# OpenProg-18F2550-etch-it.net
KiCad netlist of a schematic drawn in EAGLE
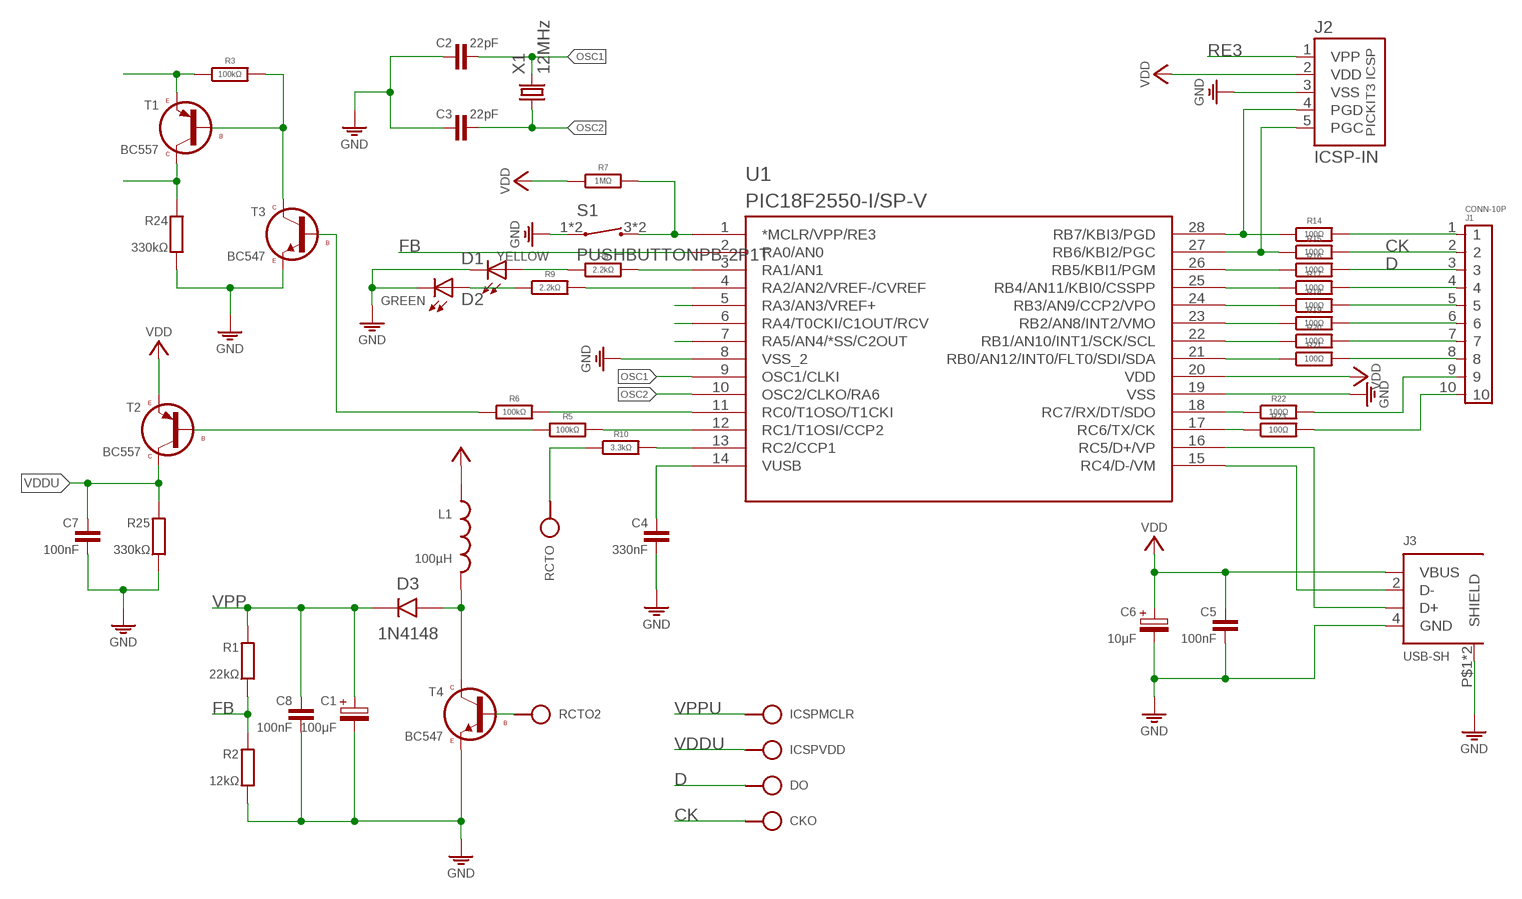
[diagram p0: schematic, sheet 1]

(export (version "E")
  (design (tool "Eeschema 10.0.6"))
  (components
    (comp (ref "C1")
      (value "100μF")
      (footprint "eagle-import:E2,5-5_V")
      (libsource (lib "eagle-import") (part "CPOLE2,5-5/V"))
    )
    (comp (ref "C2")
      (value "22pF")
      (footprint "eagle-import:C025-015X024")
      (libsource (lib "eagle-import") (part "C-H025-015X024"))
    )
    (comp (ref "C3")
      (value "22pF")
      (footprint "eagle-import:C025-015X024")
      (libsource (lib "eagle-import") (part "C-H025-015X024"))
    )
    (comp (ref "C4")
      (value "330nF")
      (footprint "eagle-import:C050-030X075")
      (libsource (lib "eagle-import") (part "C050-030X075"))
    )
    (comp (ref "C5")
      (value "100nF")
      (footprint "eagle-import:C025-015X024")
      (libsource (lib "eagle-import") (part "C025-015X024"))
    )
    (comp (ref "C6")
      (value "10μF")
      (footprint "eagle-import:E2,5-5")
      (libsource (lib "eagle-import") (part "CPOLE2.5-5"))
    )
    (comp (ref "C7")
      (value "100nF")
      (footprint "eagle-import:C050-020X036")
      (libsource (lib "eagle-import") (part "C050-020X036"))
    )
    (comp (ref "C8")
      (value "100nF")
      (footprint "eagle-import:C025-015X024")
      (libsource (lib "eagle-import") (part "C025-015X024"))
    )
    (comp (ref "CKO")
      (value "HPORT")
      (footprint "eagle-import:SPAD")
      (libsource (lib "eagle-import") (part "HPORT"))
    )
    (comp (ref "D1")
      (value "YELLOW")
      (footprint "eagle-import:LED_3MM")
      (libsource (lib "eagle-import") (part "LED-3MM"))
    )
    (comp (ref "D2")
      (value "GREEN")
      (footprint "eagle-import:LED_3MM")
      (libsource (lib "eagle-import") (part "LED-3MM"))
    )
    (comp (ref "D3")
      (value "1N4148")
      (footprint "eagle-import:DO34-7")
      (libsource (lib "eagle-import") (part "1N4148-HDO34-7"))
    )
    (comp (ref "DO")
      (value "HPORT")
      (footprint "eagle-import:SPAD")
      (libsource (lib "eagle-import") (part "HPORT"))
    )
    (comp (ref "ICSPMCLR")
      (value "HPORT")
      (footprint "eagle-import:SPAD")
      (libsource (lib "eagle-import") (part "HPORT"))
    )
    (comp (ref "ICSPVDD")
      (value "HPORT")
      (footprint "eagle-import:SPAD")
      (libsource (lib "eagle-import") (part "HPORT"))
    )
    (comp (ref "J1")
      (value "CONN-10P")
      (footprint "eagle-import:CONN-10P")
      (libsource (lib "eagle-import") (part "CONN-10P"))
    )
    (comp (ref "J2")
      (value "ICSP-IN")
      (footprint "eagle-import:PIC-PK3")
      (libsource (lib "eagle-import") (part "PICKIT3-ICSP-PK3"))
    )
    (comp (ref "J3")
      (value "USB-SH")
      (footprint "eagle-import:USB-B-PRINT")
      (libsource (lib "eagle-import") (part "USB-SH"))
    )
    (comp (ref "L1")
      (value "100µH")
      (footprint "eagle-import:L-03_10V")
      (libsource (lib "eagle-import") (part "L02/10"))
    )
    (comp (ref "R1")
      (value "22kΩ")
      (footprint "eagle-import:0204_10-V")
      (libsource (lib "eagle-import") (part "R0204/10-V"))
    )
    (comp (ref "R2")
      (value "12kΩ")
      (footprint "eagle-import:0204_10-V")
      (libsource (lib "eagle-import") (part "R0204/10-V"))
    )
    (comp (ref "R3")
      (value "100kΩ")
      (footprint "eagle-import:0204_2")
      (libsource (lib "eagle-import") (part "R-H0204/2"))
    )
    (comp (ref "R5")
      (value "100kΩ")
      (footprint "eagle-import:0204_10")
      (libsource (lib "eagle-import") (part "R-H0204/10"))
    )
    (comp (ref "R6")
      (value "100kΩ")
      (footprint "eagle-import:0204_10")
      (libsource (lib "eagle-import") (part "R-H0204/10"))
    )
    (comp (ref "R7")
      (value "1MΩ")
      (footprint "eagle-import:0204_10-V")
      (libsource (lib "eagle-import") (part "R-H0204/10-V"))
    )
    (comp (ref "R8")
      (value "2.2kΩ")
      (footprint "eagle-import:0204_10")
      (libsource (lib "eagle-import") (part "R-H0204/10"))
    )
    (comp (ref "R9")
      (value "2.2kΩ")
      (footprint "eagle-import:0204_10")
      (libsource (lib "eagle-import") (part "R-H0204/10"))
    )
    (comp (ref "R10")
      (value "3.3kΩ")
      (footprint "eagle-import:0204_10")
      (libsource (lib "eagle-import") (part "R-H0204/10"))
    )
    (comp (ref "R14")
      (value "100Ω")
      (footprint "eagle-import:0204_10")
      (libsource (lib "eagle-import") (part "R-H0204/10"))
    )
    (comp (ref "R15")
      (value "100Ω")
      (footprint "eagle-import:0204_10")
      (libsource (lib "eagle-import") (part "R-H0204/10"))
    )
    (comp (ref "R16")
      (value "100Ω")
      (footprint "eagle-import:0204_10")
      (libsource (lib "eagle-import") (part "R-H0204/10"))
    )
    (comp (ref "R17")
      (value "100Ω")
      (footprint "eagle-import:0204_10")
      (libsource (lib "eagle-import") (part "R-H0204/10"))
    )
    (comp (ref "R18")
      (value "100Ω")
      (footprint "eagle-import:0204_10")
      (libsource (lib "eagle-import") (part "R-H0204/10"))
    )
    (comp (ref "R19")
      (value "100Ω")
      (footprint "eagle-import:0204_10")
      (libsource (lib "eagle-import") (part "R-H0204/10"))
    )
    (comp (ref "R20")
      (value "100Ω")
      (footprint "eagle-import:0204_10")
      (libsource (lib "eagle-import") (part "R-H0204/10"))
    )
    (comp (ref "R21")
      (value "100Ω")
      (footprint "eagle-import:0204_10")
      (libsource (lib "eagle-import") (part "R-H0204/10"))
    )
    (comp (ref "R22")
      (value "100Ω")
      (footprint "eagle-import:0204_10")
      (libsource (lib "eagle-import") (part "R-H0204/10"))
    )
    (comp (ref "R23")
      (value "100Ω")
      (footprint "eagle-import:0204_10")
      (libsource (lib "eagle-import") (part "R-H0204/10"))
    )
    (comp (ref "R24")
      (value "330kΩ")
      (footprint "eagle-import:0204_10-V")
      (libsource (lib "eagle-import") (part "R0204/10-V"))
    )
    (comp (ref "R25")
      (value "330kΩ")
      (footprint "eagle-import:0204_10-V")
      (libsource (lib "eagle-import") (part "R0204/10-V"))
    )
    (comp (ref "RCTO")
      (value "HPORT")
      (footprint "eagle-import:SPAD")
      (libsource (lib "eagle-import") (part "HPORT"))
    )
    (comp (ref "RCTO2")
      (value "HPORT")
      (footprint "eagle-import:SPAD")
      (libsource (lib "eagle-import") (part "HPORT"))
    )
    (comp (ref "S1")
      (value "PUSHBUTTONPB-2P1T")
      (footprint "eagle-import:PB-2P1T")
      (libsource (lib "eagle-import") (part "PUSHBUTTONPB-2P1T"))
    )
    (comp (ref "T1")
      (value "BC557")
      (footprint "eagle-import:TO92-CBE")
      (libsource (lib "eagle-import") (part "BC557CBE"))
    )
    (comp (ref "T2")
      (value "BC557")
      (footprint "eagle-import:TO92-CBE")
      (libsource (lib "eagle-import") (part "BC557CBE"))
    )
    (comp (ref "T3")
      (value "BC547")
      (footprint "eagle-import:TO92")
      (libsource (lib "eagle-import") (part "BC547"))
    )
    (comp (ref "T4")
      (value "BC547")
      (footprint "eagle-import:TO92")
      (libsource (lib "eagle-import") (part "BC547"))
    )
    (comp (ref "U1")
      (value "PIC18F2550-I/SP-V")
      (footprint "eagle-import:DIL28-3_V")
      (libsource (lib "eagle-import") (part "PIC18F2550-I/SP-V"))
    )
    (comp (ref "X1")
      (value "12MHz")
      (footprint "eagle-import:HC49")
      (libsource (lib "eagle-import") (part "CRYSTALHC49"))
    )
  )
  (nets
    (net (code "1") (name "/CK") (class "Default")
      (node (ref "CKO") (pin "1") (pinfunction "P$1_1") (pintype "passive"))
      (node (ref "J1") (pin "2") (pinfunction "2_2") (pintype "passive"))
      (node (ref "R15") (pin "2") (pinfunction "2_2") (pintype "passive"))
    )
    (net (code "2") (name "/D") (class "Default")
      (node (ref "DO") (pin "1") (pinfunction "P$1_1") (pintype "passive"))
      (node (ref "J1") (pin "3") (pinfunction "3_3") (pintype "passive"))
      (node (ref "R16") (pin "2") (pinfunction "2_2") (pintype "passive"))
    )
    (net (code "3") (name "/FB") (class "Default")
      (node (ref "R1") (pin "2") (pinfunction "1_2") (pintype "passive"))
      (node (ref "R2") (pin "1") (pinfunction "2_1") (pintype "passive"))
      (node (ref "U1") (pin "2") (pinfunction "RA0/AN0_2") (pintype "passive"))
    )
    (net (code "4") (name "/RE3") (class "Default")
      (node (ref "J2") (pin "1") (pinfunction "VPP_1") (pintype "passive"))
      (node (ref "R7") (pin "2") (pinfunction "2_2") (pintype "passive"))
      (node (ref "S1") (pin "3") (pinfunction "2_3") (pintype "passive"))
      (node (ref "S1") (pin "4") (pinfunction "2_4") (pintype "passive"))
      (node (ref "U1") (pin "1") (pinfunction "*MCLR/VPP/RE3_1") (pintype "passive"))
    )
    (net (code "5") (name "/VPP") (class "Default")
      (node (ref "C1") (pin "+") (pinfunction "+_+") (pintype "passive"))
      (node (ref "C8") (pin "1") (pinfunction "1_1") (pintype "passive"))
      (node (ref "D3") (pin "C") (pinfunction "C_C") (pintype "passive"))
      (node (ref "R1") (pin "1") (pinfunction "2_1") (pintype "passive"))
      (node (ref "R3") (pin "1") (pinfunction "1_1") (pintype "passive"))
      (node (ref "T1") (pin "3") (pinfunction "E_3") (pintype "passive"))
    )
    (net (code "6") (name "/VPPU") (class "Default")
      (node (ref "ICSPMCLR") (pin "1") (pinfunction "P$1_1") (pintype "passive"))
      (node (ref "R24") (pin "1") (pinfunction "2_1") (pintype "passive"))
      (node (ref "T1") (pin "1") (pinfunction "C_1") (pintype "passive"))
    )
    (net (code "7") (name "GND") (class "Default")
      (node (ref "C1") (pin "-") (pinfunction "-_-") (pintype "passive"))
      (node (ref "C2") (pin "1") (pinfunction "1_1") (pintype "passive"))
      (node (ref "C3") (pin "1") (pinfunction "1_1") (pintype "passive"))
      (node (ref "C4") (pin "2") (pinfunction "2_2") (pintype "passive"))
      (node (ref "C5") (pin "2") (pinfunction "2_2") (pintype "passive"))
      (node (ref "C6") (pin "-") (pinfunction "-_-") (pintype "passive"))
      (node (ref "C7") (pin "2") (pinfunction "2_2") (pintype "passive"))
      (node (ref "C8") (pin "2") (pinfunction "2_2") (pintype "passive"))
      (node (ref "D1") (pin "K") (pinfunction "C_K") (pintype "passive"))
      (node (ref "D2") (pin "K") (pinfunction "C_K") (pintype "passive"))
      (node (ref "J2") (pin "3") (pinfunction "VSS_3") (pintype "passive"))
      (node (ref "J3") (pin "4") (pinfunction "GND_4") (pintype "bidirectional"))
      (node (ref "J3") (pin "P$1") (pinfunction "SHIELD_P$1") (pintype "bidirectional"))
      (node (ref "J3") (pin "P$2") (pinfunction "SHIELD_P$2") (pintype "bidirectional"))
      (node (ref "R2") (pin "2") (pinfunction "1_2") (pintype "passive"))
      (node (ref "R24") (pin "2") (pinfunction "1_2") (pintype "passive"))
      (node (ref "R25") (pin "2") (pinfunction "1_2") (pintype "passive"))
      (node (ref "S1") (pin "1") (pinfunction "1_1") (pintype "passive"))
      (node (ref "S1") (pin "2") (pinfunction "1_2") (pintype "passive"))
      (node (ref "T3") (pin "3") (pinfunction "E_3") (pintype "passive"))
      (node (ref "T4") (pin "3") (pinfunction "E_3") (pintype "passive"))
      (node (ref "U1") (pin "19") (pinfunction "VSS_19") (pintype "passive"))
      (node (ref "U1") (pin "8") (pinfunction "VSS_2_8") (pintype "passive"))
    )
    (net (code "8") (name "Net-(D1-PadA)") (class "Default")
      (node (ref "D1") (pin "A") (pinfunction "A_A") (pintype "passive"))
      (node (ref "R8") (pin "1") (pinfunction "1_1") (pintype "passive"))
    )
    (net (code "9") (name "Net-(D2-PadA)") (class "Default")
      (node (ref "D2") (pin "A") (pinfunction "A_A") (pintype "passive"))
      (node (ref "R9") (pin "1") (pinfunction "1_1") (pintype "passive"))
    )
    (net (code "10") (name "Net-(J1-Pad1)") (class "Default")
      (node (ref "J1") (pin "1") (pinfunction "1_1") (pintype "passive"))
      (node (ref "R14") (pin "2") (pinfunction "2_2") (pintype "passive"))
    )
    (net (code "11") (name "Net-(J1-Pad4)") (class "Default")
      (node (ref "J1") (pin "4") (pinfunction "4_4") (pintype "passive"))
      (node (ref "R17") (pin "2") (pinfunction "2_2") (pintype "passive"))
    )
    (net (code "12") (name "Net-(J1-Pad5)") (class "Default")
      (node (ref "J1") (pin "5") (pinfunction "5_5") (pintype "passive"))
      (node (ref "R18") (pin "2") (pinfunction "2_2") (pintype "passive"))
    )
    (net (code "13") (name "Net-(J1-Pad6)") (class "Default")
      (node (ref "J1") (pin "6") (pinfunction "6_6") (pintype "passive"))
      (node (ref "R19") (pin "2") (pinfunction "2_2") (pintype "passive"))
    )
    (net (code "14") (name "Net-(J1-Pad7)") (class "Default")
      (node (ref "J1") (pin "7") (pinfunction "7_7") (pintype "passive"))
      (node (ref "R20") (pin "2") (pinfunction "2_2") (pintype "passive"))
    )
    (net (code "15") (name "Net-(J1-Pad8)") (class "Default")
      (node (ref "J1") (pin "8") (pinfunction "8_8") (pintype "passive"))
      (node (ref "R21") (pin "2") (pinfunction "2_2") (pintype "passive"))
    )
    (net (code "16") (name "Net-(J1-Pad9)") (class "Default")
      (node (ref "J1") (pin "9") (pinfunction "9_9") (pintype "passive"))
      (node (ref "R22") (pin "2") (pinfunction "2_2") (pintype "passive"))
    )
    (net (code "17") (name "Net-(J1-Pad10)") (class "Default")
      (node (ref "J1") (pin "10") (pinfunction "10_10") (pintype "passive"))
      (node (ref "R23") (pin "2") (pinfunction "2_2") (pintype "passive"))
    )
    (net (code "18") (name "Net-(J2-PGC)") (class "Default")
      (node (ref "J2") (pin "5") (pinfunction "PGC_5") (pintype "passive"))
      (node (ref "R15") (pin "1") (pinfunction "1_1") (pintype "passive"))
      (node (ref "U1") (pin "27") (pinfunction "RB6/KBI2/PGC_27") (pintype "passive"))
    )
    (net (code "19") (name "Net-(J2-PGD)") (class "Default")
      (node (ref "J2") (pin "4") (pinfunction "PGD_4") (pintype "passive"))
      (node (ref "R14") (pin "1") (pinfunction "1_1") (pintype "passive"))
      (node (ref "U1") (pin "28") (pinfunction "RB7/KBI3/PGD_28") (pintype "passive"))
    )
    (net (code "20") (name "Net-(J3-D+)") (class "Default")
      (node (ref "J3") (pin "3") (pinfunction "D+_3") (pintype "bidirectional"))
      (node (ref "U1") (pin "16") (pinfunction "RC5/D+/VP_16") (pintype "passive"))
    )
    (net (code "21") (name "Net-(J3-D-)") (class "Default")
      (node (ref "J3") (pin "2") (pinfunction "D-_2") (pintype "bidirectional"))
      (node (ref "U1") (pin "15") (pinfunction "RC4/D-/VM_15") (pintype "passive"))
    )
    (net (code "22") (name "Net-(RCTO-P$1)") (class "Default")
      (node (ref "R10") (pin "1") (pinfunction "1_1") (pintype "passive"))
      (node (ref "RCTO") (pin "1") (pinfunction "P$1_1") (pintype "passive"))
    )
    (net (code "23") (name "Net-(RCTO2-P$1)") (class "Default")
      (node (ref "RCTO2") (pin "1") (pinfunction "P$1_1") (pintype "passive"))
      (node (ref "T4") (pin "2") (pinfunction "B_2") (pintype "passive"))
    )
    (net (code "24") (name "Net-(T1-B)") (class "Default")
      (node (ref "R3") (pin "2") (pinfunction "2_2") (pintype "passive"))
      (node (ref "T1") (pin "2") (pinfunction "B_2") (pintype "passive"))
      (node (ref "T3") (pin "1") (pinfunction "C_1") (pintype "passive"))
    )
    (net (code "25") (name "Net-(T2-B)") (class "Default")
      (node (ref "R5") (pin "1") (pinfunction "1_1") (pintype "passive"))
      (node (ref "T2") (pin "2") (pinfunction "B_2") (pintype "passive"))
    )
    (net (code "26") (name "Net-(T3-B)") (class "Default")
      (node (ref "R6") (pin "1") (pinfunction "1_1") (pintype "passive"))
      (node (ref "T3") (pin "2") (pinfunction "B_2") (pintype "passive"))
    )
    (net (code "27") (name "Net-(T4-C)") (class "Default")
      (node (ref "D3") (pin "A") (pinfunction "A_A") (pintype "passive"))
      (node (ref "L1") (pin "2") (pinfunction "2_2") (pintype "passive"))
      (node (ref "T4") (pin "1") (pinfunction "C_1") (pintype "passive"))
    )
    (net (code "28") (name "Net-(U1-RA1{slash}AN1)") (class "Default")
      (node (ref "R8") (pin "2") (pinfunction "2_2") (pintype "passive"))
      (node (ref "U1") (pin "3") (pinfunction "RA1/AN1_3") (pintype "passive"))
    )
    (net (code "29") (name "Net-(U1-RA2{slash}AN2{slash}VREF-{slash}CVREF)") (class "Default")
      (node (ref "R9") (pin "2") (pinfunction "2_2") (pintype "passive"))
      (node (ref "U1") (pin "4") (pinfunction "RA2/AN2/VREF-/CVREF_4") (pintype "passive"))
    )
    (net (code "30") (name "Net-(U1-RB0{slash}AN12{slash}INT0{slash}FLT0{slash}SDI{slash}SDA)") (class "Default")
      (node (ref "R21") (pin "1") (pinfunction "1_1") (pintype "passive"))
      (node (ref "U1") (pin "21") (pinfunction "RB0/AN12/INT0/FLT0/SDI/SDA_21") (pintype "passive"))
    )
    (net (code "31") (name "Net-(U1-RB1{slash}AN10{slash}INT1{slash}SCK{slash}SCL)") (class "Default")
      (node (ref "R20") (pin "1") (pinfunction "1_1") (pintype "passive"))
      (node (ref "U1") (pin "22") (pinfunction "RB1/AN10/INT1/SCK/SCL_22") (pintype "passive"))
    )
    (net (code "32") (name "Net-(U1-RB2{slash}AN8{slash}INT2{slash}VMO)") (class "Default")
      (node (ref "R19") (pin "1") (pinfunction "1_1") (pintype "passive"))
      (node (ref "U1") (pin "23") (pinfunction "RB2/AN8/INT2/VMO_23") (pintype "passive"))
    )
    (net (code "33") (name "Net-(U1-RB3{slash}AN9{slash}CCP2{slash}VPO)") (class "Default")
      (node (ref "R18") (pin "1") (pinfunction "1_1") (pintype "passive"))
      (node (ref "U1") (pin "24") (pinfunction "RB3/AN9/CCP2/VPO_24") (pintype "passive"))
    )
    (net (code "34") (name "Net-(U1-RB4{slash}AN11{slash}KBI0{slash}CSSPP)") (class "Default")
      (node (ref "R17") (pin "1") (pinfunction "1_1") (pintype "passive"))
      (node (ref "U1") (pin "25") (pinfunction "RB4/AN11/KBI0/CSSPP_25") (pintype "passive"))
    )
    (net (code "35") (name "Net-(U1-RB5{slash}KBI1{slash}PGM)") (class "Default")
      (node (ref "R16") (pin "1") (pinfunction "1_1") (pintype "passive"))
      (node (ref "U1") (pin "26") (pinfunction "RB5/KBI1/PGM_26") (pintype "passive"))
    )
    (net (code "36") (name "Net-(U1-RC0{slash}T1OSO{slash}T1CKI)") (class "Default")
      (node (ref "R6") (pin "2") (pinfunction "2_2") (pintype "passive"))
      (node (ref "U1") (pin "11") (pinfunction "RC0/T1OSO/T1CKI_11") (pintype "passive"))
    )
    (net (code "37") (name "Net-(U1-RC1{slash}T1OSI{slash}CCP2)") (class "Default")
      (node (ref "R5") (pin "2") (pinfunction "2_2") (pintype "passive"))
      (node (ref "U1") (pin "12") (pinfunction "RC1/T1OSI/CCP2_12") (pintype "passive"))
    )
    (net (code "38") (name "Net-(U1-RC2{slash}CCP1)") (class "Default")
      (node (ref "R10") (pin "2") (pinfunction "2_2") (pintype "passive"))
      (node (ref "U1") (pin "13") (pinfunction "RC2/CCP1_13") (pintype "passive"))
    )
    (net (code "39") (name "Net-(U1-RC6{slash}TX{slash}CK)") (class "Default")
      (node (ref "R23") (pin "1") (pinfunction "1_1") (pintype "passive"))
      (node (ref "U1") (pin "17") (pinfunction "RC6/TX/CK_17") (pintype "passive"))
    )
    (net (code "40") (name "Net-(U1-RC7{slash}RX{slash}DT{slash}SDO)") (class "Default")
      (node (ref "R22") (pin "1") (pinfunction "1_1") (pintype "passive"))
      (node (ref "U1") (pin "18") (pinfunction "RC7/RX/DT/SDO_18") (pintype "passive"))
    )
    (net (code "41") (name "Net-(U1-VUSB)") (class "Default")
      (node (ref "C4") (pin "1") (pinfunction "1_1") (pintype "passive"))
      (node (ref "U1") (pin "14") (pinfunction "VUSB_14") (pintype "passive"))
    )
    (net (code "42") (name "OSC1") (class "Default")
      (node (ref "C2") (pin "2") (pinfunction "2_2") (pintype "passive"))
      (node (ref "U1") (pin "9") (pinfunction "OSC1/CLKI_9") (pintype "passive"))
      (node (ref "X1") (pin "2") (pinfunction "2_2") (pintype "passive"))
    )
    (net (code "43") (name "OSC2") (class "Default")
      (node (ref "C3") (pin "2") (pinfunction "2_2") (pintype "passive"))
      (node (ref "U1") (pin "10") (pinfunction "OSC2/CLKO/RA6_10") (pintype "passive"))
      (node (ref "X1") (pin "1") (pinfunction "1_1") (pintype "passive"))
    )
    (net (code "44") (name "VDD") (class "Default")
      (node (ref "C5") (pin "1") (pinfunction "1_1") (pintype "passive"))
      (node (ref "C6") (pin "+") (pinfunction "+_+") (pintype "passive"))
      (node (ref "J2") (pin "2") (pinfunction "VDD_2") (pintype "passive"))
      (node (ref "J3") (pin "1") (pinfunction "VBUS_1") (pintype "bidirectional"))
      (node (ref "L1") (pin "1") (pinfunction "1_1") (pintype "passive"))
      (node (ref "R7") (pin "1") (pinfunction "1_1") (pintype "passive"))
      (node (ref "T2") (pin "3") (pinfunction "E_3") (pintype "passive"))
      (node (ref "U1") (pin "20") (pinfunction "VDD_20") (pintype "passive"))
    )
    (net (code "45") (name "VDDU") (class "Default")
      (node (ref "C7") (pin "1") (pinfunction "1_1") (pintype "passive"))
      (node (ref "ICSPVDD") (pin "1") (pinfunction "P$1_1") (pintype "passive"))
      (node (ref "R25") (pin "1") (pinfunction "2_1") (pintype "passive"))
      (node (ref "T2") (pin "1") (pinfunction "C_1") (pintype "passive"))
    )
    (net (code "46") (name "unconnected-(U1-RA3{slash}AN3{slash}VREF+-Pad5)") (class "Default")
      (node (ref "U1") (pin "5") (pinfunction "RA3/AN3/VREF+_5") (pintype "passive"))
    )
    (net (code "47") (name "unconnected-(U1-RA4{slash}T0CKI{slash}C1OUT{slash}RCV-Pad6)") (class "Default")
      (node (ref "U1") (pin "6") (pinfunction "RA4/T0CKI/C1OUT/RCV_6") (pintype "passive"))
    )
    (net (code "48") (name "unconnected-(U1-RA5{slash}AN4{slash}*SS{slash}C2OUT-Pad7)") (class "Default")
      (node (ref "U1") (pin "7") (pinfunction "RA5/AN4/*SS/C2OUT_7") (pintype "passive"))
    )
  )
)
